# MAX2831_2024_REUSE.net
KiCad netlist of a schematic drawn in EasyEDA Pro
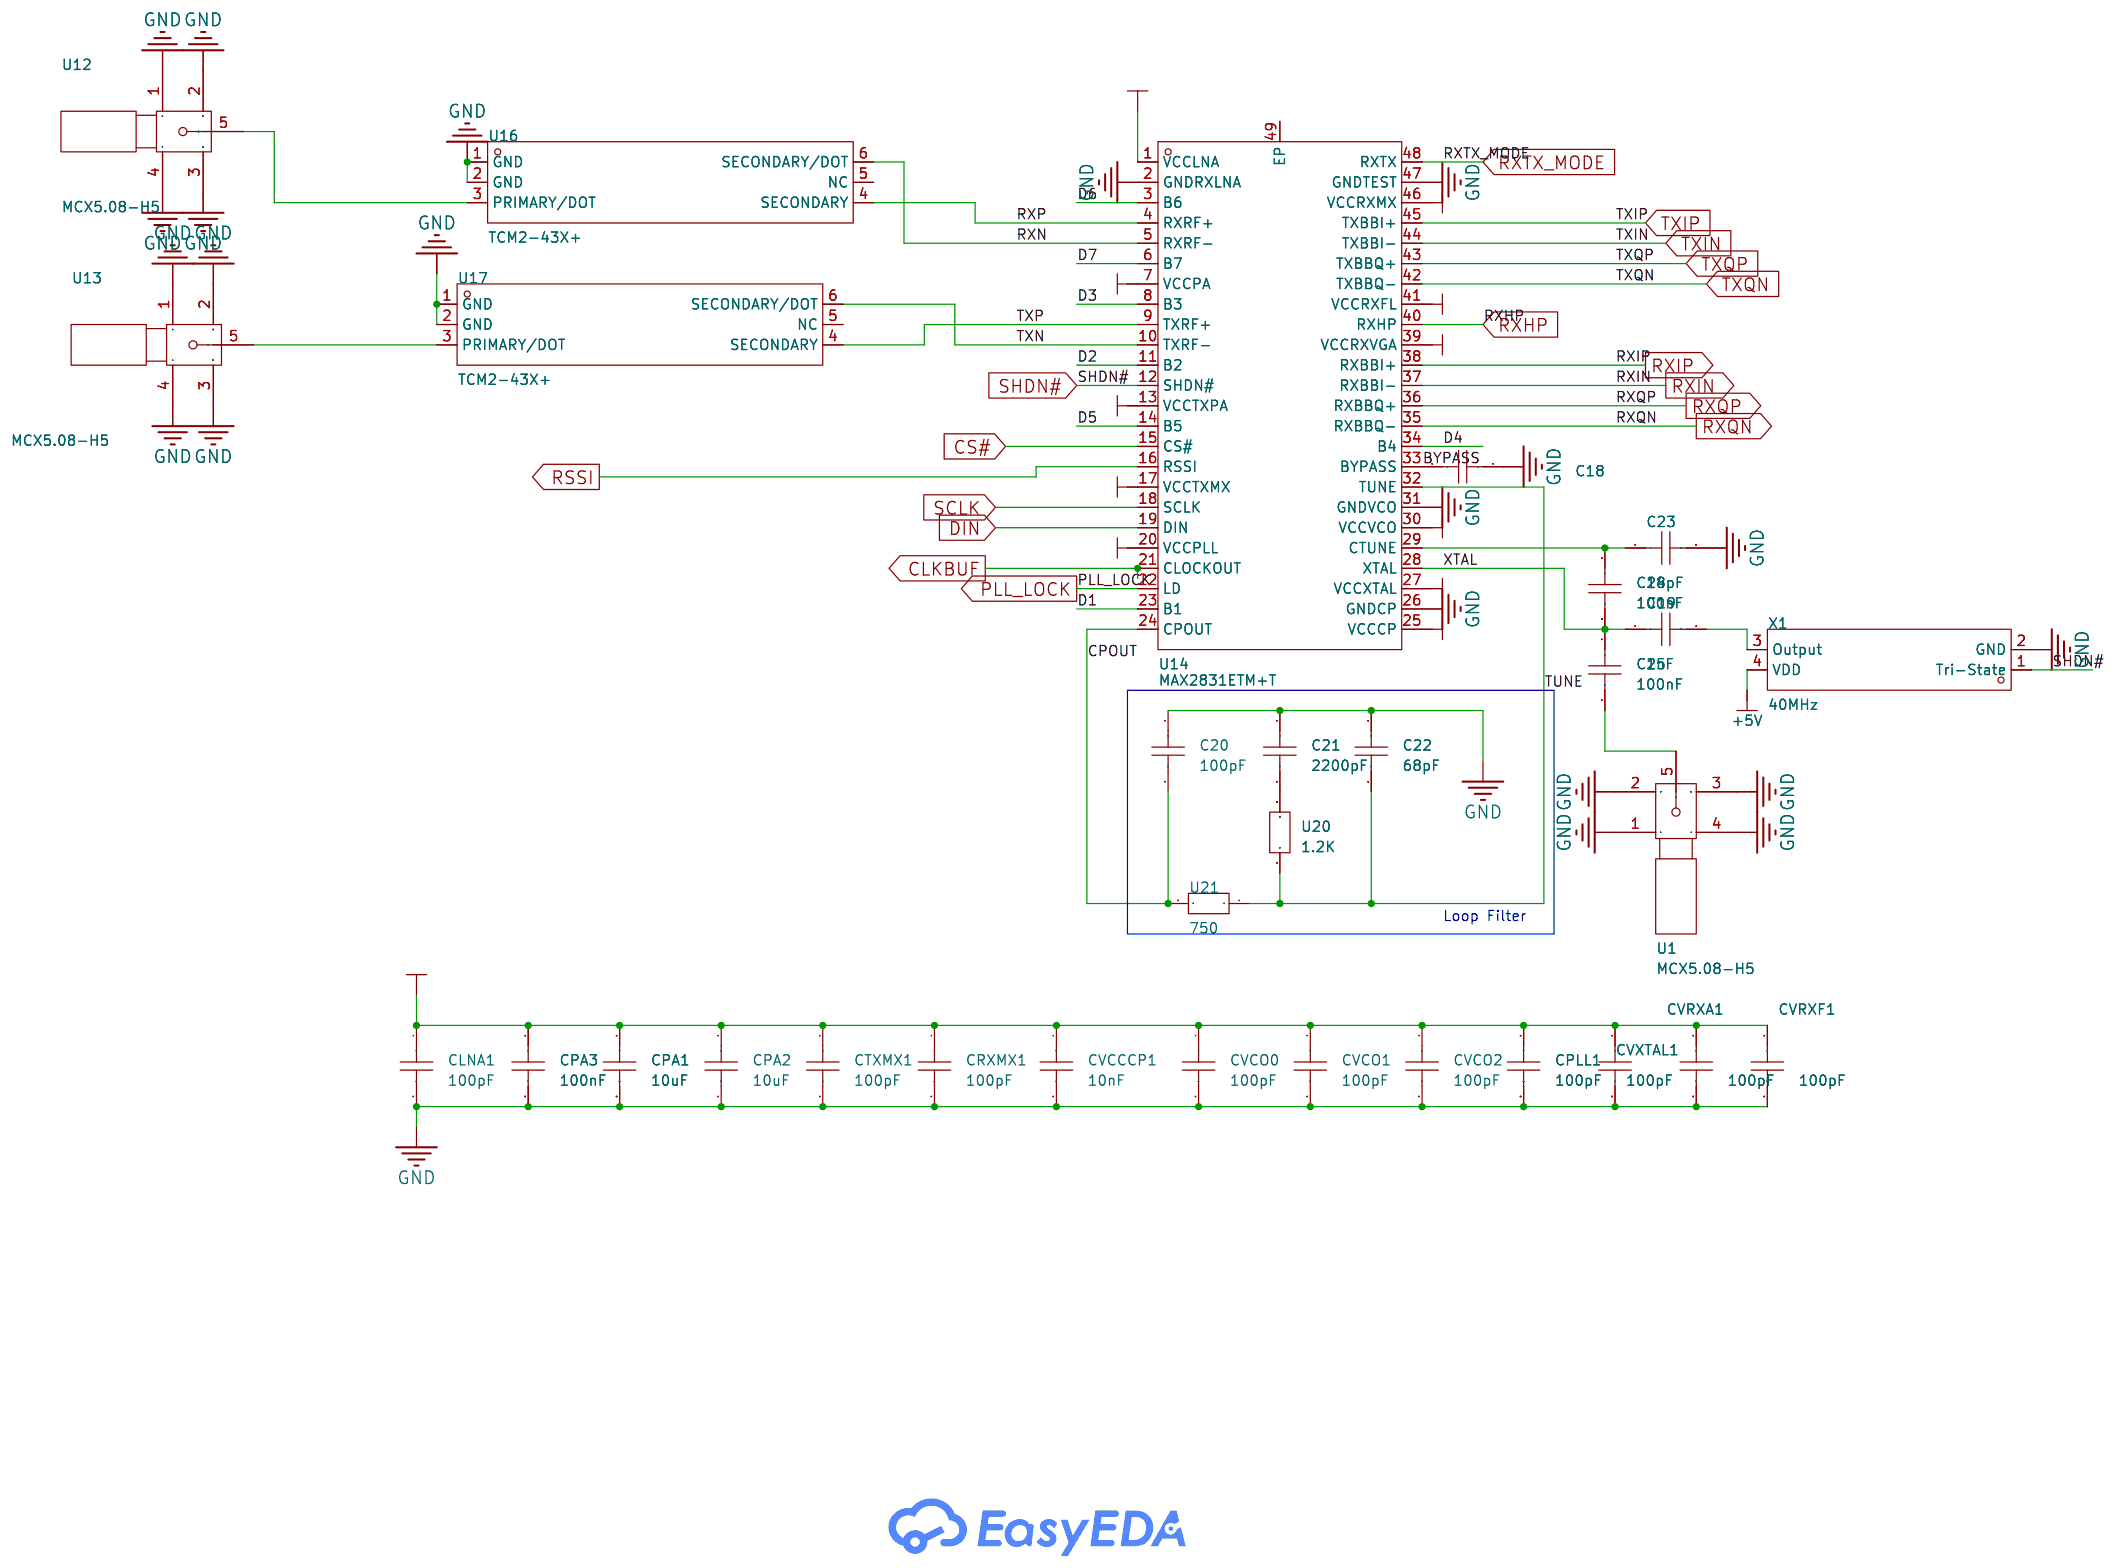
[diagram p0: schematic sheet]

(export (version "E")
  (design (tool "Eeschema 10.0.6"))
  (components
    (comp (ref "C18")
      (value "100nF")
      (footprint "easyedapro:C0805")
      (libsource (lib "easyedapro") (part "CAP"))
    )
    (comp (ref "C19")
      (value "1nF")
      (footprint "easyedapro:C0805")
      (libsource (lib "easyedapro") (part "CAP"))
    )
    (comp (ref "C20")
      (value "100pF")
      (footprint "easyedapro:C0805")
      (libsource (lib "easyedapro") (part "CAP"))
    )
    (comp (ref "C21")
      (value "2200pF")
      (footprint "easyedapro:C0805")
      (libsource (lib "easyedapro") (part "CAP"))
    )
    (comp (ref "C22")
      (value "68pF")
      (footprint "easyedapro:C0805")
      (libsource (lib "easyedapro") (part "CAP"))
    )
    (comp (ref "C23")
      (value "18pF")
      (footprint "easyedapro:C0805")
      (libsource (lib "easyedapro") (part "CAP"))
    )
    (comp (ref "C24")
      (value "100nF")
      (footprint "easyedapro:C0805")
      (libsource (lib "easyedapro") (part "CAP"))
    )
    (comp (ref "C25")
      (value "100nF")
      (footprint "easyedapro:C0805")
      (libsource (lib "easyedapro") (part "CAP"))
    )
    (comp (ref "CLNA1")
      (value "100pF")
      (footprint "easyedapro:C0805")
      (libsource (lib "easyedapro") (part "CAP"))
    )
    (comp (ref "CPA1")
      (value "10uF")
      (footprint "easyedapro:C0805")
      (libsource (lib "easyedapro") (part "CAP"))
    )
    (comp (ref "CPA2")
      (value "10uF")
      (footprint "easyedapro:C0805")
      (libsource (lib "easyedapro") (part "CAP"))
    )
    (comp (ref "CPA3")
      (value "100nF")
      (footprint "easyedapro:C0805")
      (libsource (lib "easyedapro") (part "CAP"))
    )
    (comp (ref "CPLL1")
      (value "100pF")
      (footprint "easyedapro:C0805")
      (libsource (lib "easyedapro") (part "CAP"))
    )
    (comp (ref "CRXMX1")
      (value "100pF")
      (footprint "easyedapro:C0805")
      (libsource (lib "easyedapro") (part "CAP"))
    )
    (comp (ref "CTXMX1")
      (value "100pF")
      (footprint "easyedapro:C0805")
      (libsource (lib "easyedapro") (part "CAP"))
    )
    (comp (ref "CVCCCP1")
      (value "10nF")
      (footprint "easyedapro:C0805")
      (libsource (lib "easyedapro") (part "CAP"))
    )
    (comp (ref "CVCO0")
      (value "100pF")
      (footprint "easyedapro:C0805")
      (libsource (lib "easyedapro") (part "CAP"))
    )
    (comp (ref "CVCO1")
      (value "100pF")
      (footprint "easyedapro:C0805")
      (libsource (lib "easyedapro") (part "CAP"))
    )
    (comp (ref "CVCO2")
      (value "100pF")
      (footprint "easyedapro:C0805")
      (libsource (lib "easyedapro") (part "CAP"))
    )
    (comp (ref "CVRXA1")
      (value "100pF")
      (footprint "easyedapro:C0805")
      (libsource (lib "easyedapro") (part "CAP"))
    )
    (comp (ref "CVRXF1")
      (value "100pF")
      (footprint "easyedapro:C0805")
      (libsource (lib "easyedapro") (part "CAP"))
    )
    (comp (ref "CVXTAL1")
      (value "100pF")
      (footprint "easyedapro:C0805")
      (libsource (lib "easyedapro") (part "CAP"))
    )
    (comp (ref "U1")
      (value "MCX5.08-H5")
      (footprint "easyedapro:SMA-TH_MCX5.08-H5")
      (libsource (lib "easyedapro") (part "MCX5.08-H5_C9900009324"))
    )
    (comp (ref "U12")
      (value "MCX5.08-H5")
      (footprint "easyedapro:SMA-TH_MCX5.08-H5")
      (libsource (lib "easyedapro") (part "MCX5.08-H5_C9900009324"))
    )
    (comp (ref "U13")
      (value "MCX5.08-H5")
      (footprint "easyedapro:SMA-TH_MCX5.08-H5")
      (libsource (lib "easyedapro") (part "MCX5.08-H5_C9900009324"))
    )
    (comp (ref "U14")
      (value "MAX2831ETM+T")
      (footprint "easyedapro:TQFN-48_L7.0-W7.0-P0.50-TL-EP5.6")
      (fields (field (name "Manufacturer") "ADI(亚德诺)/MAXIM(美信)"))
      (libsource (lib "easyedapro") (part "MAX2831ETM+T"))
    )
    (comp (ref "U16")
      (value "TCM2-43X+")
      (footprint "easyedapro:IND-SMD_6P-L4.1-W3.8-P1.27-TL")
      (fields (field (name "Manufacturer") "Mini-Circuits"))
      (libsource (lib "easyedapro") (part "TCM2-43X+"))
    )
    (comp (ref "U17")
      (value "TCM2-43X+")
      (footprint "easyedapro:IND-SMD_6P-L4.1-W3.8-P1.27-TL")
      (fields (field (name "Manufacturer") "Mini-Circuits"))
      (libsource (lib "easyedapro") (part "TCM2-43X+"))
    )
    (comp (ref "U20")
      (value "1.2K")
      (footprint "easyedapro:R0805")
      (fields (field (name "Manufacturer Part") "SCR0805J1M") (field (name "Manufacturer") "VO(翔胜)"))
      (libsource (lib "easyedapro") (part "SCR0805J1M"))
    )
    (comp (ref "U21")
      (value "750")
      (footprint "easyedapro:R0805")
      (fields (field (name "Manufacturer Part") "SCR0805J1M") (field (name "Manufacturer") "VO(翔胜)"))
      (libsource (lib "easyedapro") (part "SCR0805J1M"))
    )
    (comp (ref "X1")
      (value "40MHz")
      (footprint "easyedapro:OSC-SMD_4P-L3.2-W2.5-BL")
      (fields
        (field (name "Manufacturer Part") "SX3M40.000E20F30THN")
        (field (name "Manufacturer") "SCTF(星通时频)")
      )
      (libsource (lib "easyedapro") (part "SX3M40.000E20F30THN"))
    )
  )
  (nets
    (net (code "1") (name "+5V") (class "Default")
      (node (ref "X1") (pin "4") (pinfunction "VDD_4") (pintype "unspecified"))
    )
    (net (code "2") (name "/BYPASS") (class "Default")
      (node (ref "C18") (pin "2") (pinfunction "2_2") (pintype "input"))
      (node (ref "U14") (pin "33") (pinfunction "BYPASS_33") (pintype "unspecified"))
    )
    (net (code "3") (name "/CPOUT") (class "Default")
      (node (ref "C20") (pin "2") (pinfunction "2_2") (pintype "input"))
      (node (ref "U14") (pin "24") (pinfunction "CPOUT_24") (pintype "unspecified"))
      (node (ref "U21") (pin "2") (pinfunction "2_2") (pintype "unspecified"))
    )
    (net (code "4") (name "/D1") (class "Default")
      (node (ref "U14") (pin "23") (pinfunction "B1_23") (pintype "unspecified"))
    )
    (net (code "5") (name "/D2") (class "Default")
      (node (ref "U14") (pin "11") (pinfunction "B2_11") (pintype "unspecified"))
    )
    (net (code "6") (name "/D3") (class "Default")
      (node (ref "U14") (pin "8") (pinfunction "B3_8") (pintype "unspecified"))
    )
    (net (code "7") (name "/D4") (class "Default")
      (node (ref "U14") (pin "34") (pinfunction "B4_34") (pintype "unspecified"))
    )
    (net (code "8") (name "/D5") (class "Default")
      (node (ref "U14") (pin "14") (pinfunction "B5_14") (pintype "unspecified"))
    )
    (net (code "9") (name "/D6") (class "Default")
      (node (ref "U14") (pin "3") (pinfunction "B6_3") (pintype "unspecified"))
    )
    (net (code "10") (name "/D7") (class "Default")
      (node (ref "U14") (pin "6") (pinfunction "B7_6") (pintype "unspecified"))
    )
    (net (code "11") (name "/RXN") (class "Default")
      (node (ref "U14") (pin "5") (pinfunction "RXRF-_5") (pintype "unspecified"))
      (node (ref "U16") (pin "6") (pinfunction "SECONDARY/DOT_6") (pintype "input"))
    )
    (net (code "12") (name "/RXP") (class "Default")
      (node (ref "U14") (pin "4") (pinfunction "RXRF+_4") (pintype "unspecified"))
      (node (ref "U16") (pin "4") (pinfunction "SECONDARY_4") (pintype "input"))
    )
    (net (code "13") (name "/TUNE") (class "Default")
      (node (ref "C22") (pin "2") (pinfunction "2_2") (pintype "input"))
      (node (ref "U14") (pin "32") (pinfunction "TUNE_32") (pintype "unspecified"))
      (node (ref "U20") (pin "1") (pinfunction "1_1") (pintype "unspecified"))
      (node (ref "U21") (pin "1") (pinfunction "1_1") (pintype "unspecified"))
    )
    (net (code "14") (name "/TXN") (class "Default")
      (node (ref "U14") (pin "10") (pinfunction "TXRF-_10") (pintype "unspecified"))
      (node (ref "U17") (pin "6") (pinfunction "SECONDARY/DOT_6") (pintype "input"))
    )
    (net (code "15") (name "/TXP") (class "Default")
      (node (ref "U14") (pin "9") (pinfunction "TXRF+_9") (pintype "unspecified"))
      (node (ref "U17") (pin "4") (pinfunction "SECONDARY_4") (pintype "input"))
    )
    (net (code "16") (name "/XTAL") (class "Default")
      (node (ref "C19") (pin "2") (pinfunction "2_2") (pintype "input"))
      (node (ref "C24") (pin "2") (pinfunction "2_2") (pintype "input"))
      (node (ref "C25") (pin "1") (pinfunction "1_1") (pintype "input"))
      (node (ref "U14") (pin "28") (pinfunction "XTAL_28") (pintype "unspecified"))
    )
    (net (code "17") (name "3.3") (class "Default")
      (node (ref "CLNA1") (pin "1") (pinfunction "1_1") (pintype "input"))
      (node (ref "CPA1") (pin "1") (pinfunction "1_1") (pintype "input"))
      (node (ref "CPA2") (pin "1") (pinfunction "1_1") (pintype "input"))
      (node (ref "CPA3") (pin "1") (pinfunction "1_1") (pintype "input"))
      (node (ref "CPLL1") (pin "1") (pinfunction "1_1") (pintype "input"))
      (node (ref "CRXMX1") (pin "1") (pinfunction "1_1") (pintype "input"))
      (node (ref "CTXMX1") (pin "1") (pinfunction "1_1") (pintype "input"))
      (node (ref "CVCCCP1") (pin "1") (pinfunction "1_1") (pintype "input"))
      (node (ref "CVCO0") (pin "1") (pinfunction "1_1") (pintype "input"))
      (node (ref "CVCO1") (pin "1") (pinfunction "1_1") (pintype "input"))
      (node (ref "CVCO2") (pin "1") (pinfunction "1_1") (pintype "input"))
      (node (ref "CVRXA1") (pin "1") (pinfunction "1_1") (pintype "input"))
      (node (ref "CVRXF1") (pin "1") (pinfunction "1_1") (pintype "input"))
      (node (ref "CVXTAL1") (pin "1") (pinfunction "1_1") (pintype "input"))
      (node (ref "U14") (pin "1") (pinfunction "VCCLNA_1") (pintype "unspecified"))
      (node (ref "U14") (pin "13") (pinfunction "VCCTXPA_13") (pintype "unspecified"))
      (node (ref "U14") (pin "17") (pinfunction "VCCTXMX_17") (pintype "unspecified"))
      (node (ref "U14") (pin "20") (pinfunction "VCCPLL_20") (pintype "unspecified"))
      (node (ref "U14") (pin "25") (pinfunction "VCCCP_25") (pintype "unspecified"))
      (node (ref "U14") (pin "27") (pinfunction "VCCXTAL_27") (pintype "unspecified"))
      (node (ref "U14") (pin "30") (pinfunction "VCCVCO_30") (pintype "unspecified"))
      (node (ref "U14") (pin "39") (pinfunction "VCCRXVGA_39") (pintype "unspecified"))
      (node (ref "U14") (pin "41") (pinfunction "VCCRXFL_41") (pintype "unspecified"))
      (node (ref "U14") (pin "46") (pinfunction "VCCRXMX_46") (pintype "unspecified"))
      (node (ref "U14") (pin "7") (pinfunction "VCCPA_7") (pintype "unspecified"))
    )
    (net (code "18") (name "CLKBUF") (class "Default")
      (node (ref "U14") (pin "21") (pinfunction "CLOCKOUT_21") (pintype "unspecified"))
    )
    (net (code "19") (name "CS#") (class "Default")
      (node (ref "U14") (pin "15") (pinfunction "CS#_15") (pintype "unspecified"))
    )
    (net (code "20") (name "DIN") (class "Default")
      (node (ref "U14") (pin "19") (pinfunction "DIN_19") (pintype "unspecified"))
    )
    (net (code "21") (name "GND") (class "Default")
      (node (ref "C18") (pin "1") (pinfunction "1_1") (pintype "input"))
      (node (ref "C20") (pin "1") (pinfunction "1_1") (pintype "input"))
      (node (ref "C21") (pin "1") (pinfunction "1_1") (pintype "input"))
      (node (ref "C22") (pin "1") (pinfunction "1_1") (pintype "input"))
      (node (ref "C23") (pin "2") (pinfunction "2_2") (pintype "input"))
      (node (ref "CLNA1") (pin "2") (pinfunction "2_2") (pintype "input"))
      (node (ref "CPA1") (pin "2") (pinfunction "2_2") (pintype "input"))
      (node (ref "CPA2") (pin "2") (pinfunction "2_2") (pintype "input"))
      (node (ref "CPA3") (pin "2") (pinfunction "2_2") (pintype "input"))
      (node (ref "CPLL1") (pin "2") (pinfunction "2_2") (pintype "input"))
      (node (ref "CRXMX1") (pin "2") (pinfunction "2_2") (pintype "input"))
      (node (ref "CTXMX1") (pin "2") (pinfunction "2_2") (pintype "input"))
      (node (ref "CVCCCP1") (pin "2") (pinfunction "2_2") (pintype "input"))
      (node (ref "CVCO0") (pin "2") (pinfunction "2_2") (pintype "input"))
      (node (ref "CVCO1") (pin "2") (pinfunction "2_2") (pintype "input"))
      (node (ref "CVCO2") (pin "2") (pinfunction "2_2") (pintype "input"))
      (node (ref "CVRXA1") (pin "2") (pinfunction "2_2") (pintype "input"))
      (node (ref "CVRXF1") (pin "2") (pinfunction "2_2") (pintype "input"))
      (node (ref "CVXTAL1") (pin "2") (pinfunction "2_2") (pintype "input"))
      (node (ref "U1") (pin "1") (pinfunction "1_1") (pintype "unspecified"))
      (node (ref "U1") (pin "2") (pinfunction "2_2") (pintype "unspecified"))
      (node (ref "U1") (pin "3") (pinfunction "3_3") (pintype "unspecified"))
      (node (ref "U1") (pin "4") (pinfunction "4_4") (pintype "unspecified"))
      (node (ref "U12") (pin "1") (pinfunction "1_1") (pintype "unspecified"))
      (node (ref "U12") (pin "2") (pinfunction "2_2") (pintype "unspecified"))
      (node (ref "U12") (pin "3") (pinfunction "3_3") (pintype "unspecified"))
      (node (ref "U12") (pin "4") (pinfunction "4_4") (pintype "unspecified"))
      (node (ref "U13") (pin "1") (pinfunction "1_1") (pintype "unspecified"))
      (node (ref "U13") (pin "2") (pinfunction "2_2") (pintype "unspecified"))
      (node (ref "U13") (pin "3") (pinfunction "3_3") (pintype "unspecified"))
      (node (ref "U13") (pin "4") (pinfunction "4_4") (pintype "unspecified"))
      (node (ref "U14") (pin "2") (pinfunction "GNDRXLNA_2") (pintype "unspecified"))
      (node (ref "U14") (pin "26") (pinfunction "GNDCP_26") (pintype "unspecified"))
      (node (ref "U14") (pin "31") (pinfunction "GNDVCO_31") (pintype "unspecified"))
      (node (ref "U14") (pin "47") (pinfunction "GNDTEST_47") (pintype "unspecified"))
      (node (ref "U16") (pin "1") (pinfunction "GND_1") (pintype "input"))
      (node (ref "U16") (pin "2") (pinfunction "GND_2") (pintype "input"))
      (node (ref "U17") (pin "1") (pinfunction "GND_1") (pintype "input"))
      (node (ref "U17") (pin "2") (pinfunction "GND_2") (pintype "input"))
      (node (ref "X1") (pin "2") (pinfunction "GND_2") (pintype "unspecified"))
    )
    (net (code "22") (name "Net-(C21-Pad2)") (class "Default")
      (node (ref "C21") (pin "2") (pinfunction "2_2") (pintype "input"))
      (node (ref "U20") (pin "2") (pinfunction "2_2") (pintype "unspecified"))
    )
    (net (code "23") (name "Net-(C25-Pad2)") (class "Default")
      (node (ref "C25") (pin "2") (pinfunction "2_2") (pintype "input"))
      (node (ref "U1") (pin "5") (pinfunction "5_5") (pintype "unspecified"))
    )
    (net (code "24") (name "Net-(U14-CTUNE)") (class "Default")
      (node (ref "C23") (pin "1") (pinfunction "1_1") (pintype "input"))
      (node (ref "C24") (pin "1") (pinfunction "1_1") (pintype "input"))
      (node (ref "U14") (pin "29") (pinfunction "CTUNE_29") (pintype "unspecified"))
    )
    (net (code "25") (name "Net-(U16-PRIMARY{slash}DOT)") (class "Default")
      (node (ref "U12") (pin "5") (pinfunction "5_5") (pintype "unspecified"))
      (node (ref "U16") (pin "3") (pinfunction "PRIMARY/DOT_3") (pintype "input"))
    )
    (net (code "26") (name "Net-(U17-PRIMARY{slash}DOT)") (class "Default")
      (node (ref "U13") (pin "5") (pinfunction "5_5") (pintype "unspecified"))
      (node (ref "U17") (pin "3") (pinfunction "PRIMARY/DOT_3") (pintype "input"))
    )
    (net (code "27") (name "Net-(X1-Output)") (class "Default")
      (node (ref "C19") (pin "1") (pinfunction "1_1") (pintype "input"))
      (node (ref "X1") (pin "3") (pinfunction "Output_3") (pintype "unspecified"))
    )
    (net (code "28") (name "PLL_LOCK") (class "Default")
      (node (ref "U14") (pin "22") (pinfunction "LD_22") (pintype "unspecified"))
    )
    (net (code "29") (name "RSSI") (class "Default")
      (node (ref "U14") (pin "16") (pinfunction "RSSI_16") (pintype "unspecified"))
    )
    (net (code "30") (name "RXHP") (class "Default")
      (node (ref "U14") (pin "40") (pinfunction "RXHP_40") (pintype "unspecified"))
    )
    (net (code "31") (name "RXIN") (class "Default")
      (node (ref "U14") (pin "37") (pinfunction "RXBBI-_37") (pintype "unspecified"))
    )
    (net (code "32") (name "RXIP") (class "Default")
      (node (ref "U14") (pin "38") (pinfunction "RXBBI+_38") (pintype "unspecified"))
    )
    (net (code "33") (name "RXQN") (class "Default")
      (node (ref "U14") (pin "35") (pinfunction "RXBBQ-_35") (pintype "unspecified"))
    )
    (net (code "34") (name "RXQP") (class "Default")
      (node (ref "U14") (pin "36") (pinfunction "RXBBQ+_36") (pintype "unspecified"))
    )
    (net (code "35") (name "RXTX_MODE") (class "Default")
      (node (ref "U14") (pin "48") (pinfunction "RXTX_48") (pintype "unspecified"))
    )
    (net (code "36") (name "SCLK") (class "Default")
      (node (ref "U14") (pin "18") (pinfunction "SCLK_18") (pintype "unspecified"))
    )
    (net (code "37") (name "SHDN#") (class "Default")
      (node (ref "U14") (pin "12") (pinfunction "SHDN#_12") (pintype "unspecified"))
      (node (ref "X1") (pin "1") (pinfunction "Tri-State_1") (pintype "unspecified"))
    )
    (net (code "38") (name "TXIN") (class "Default")
      (node (ref "U14") (pin "44") (pinfunction "TXBBI-_44") (pintype "unspecified"))
    )
    (net (code "39") (name "TXIP") (class "Default")
      (node (ref "U14") (pin "45") (pinfunction "TXBBI+_45") (pintype "unspecified"))
    )
    (net (code "40") (name "TXQN") (class "Default")
      (node (ref "U14") (pin "42") (pinfunction "TXBBQ-_42") (pintype "unspecified"))
    )
    (net (code "41") (name "TXQP") (class "Default")
      (node (ref "U14") (pin "43") (pinfunction "TXBBQ+_43") (pintype "unspecified"))
    )
    (net (code "42") (name "unconnected-(U14-EP-Pad49)") (class "Default")
      (node (ref "U14") (pin "49") (pinfunction "EP_49") (pintype "unspecified"))
    )
    (net (code "43") (name "unconnected-(U16-NC-Pad5)") (class "Default")
      (node (ref "U16") (pin "5") (pinfunction "NC_5") (pintype "input"))
    )
    (net (code "44") (name "unconnected-(U17-NC-Pad5)") (class "Default")
      (node (ref "U17") (pin "5") (pinfunction "NC_5") (pintype "input"))
    )
  )
)
